# KGM_Feedback_v2_0.net
KiCad netlist of a schematic drawn in EAGLE
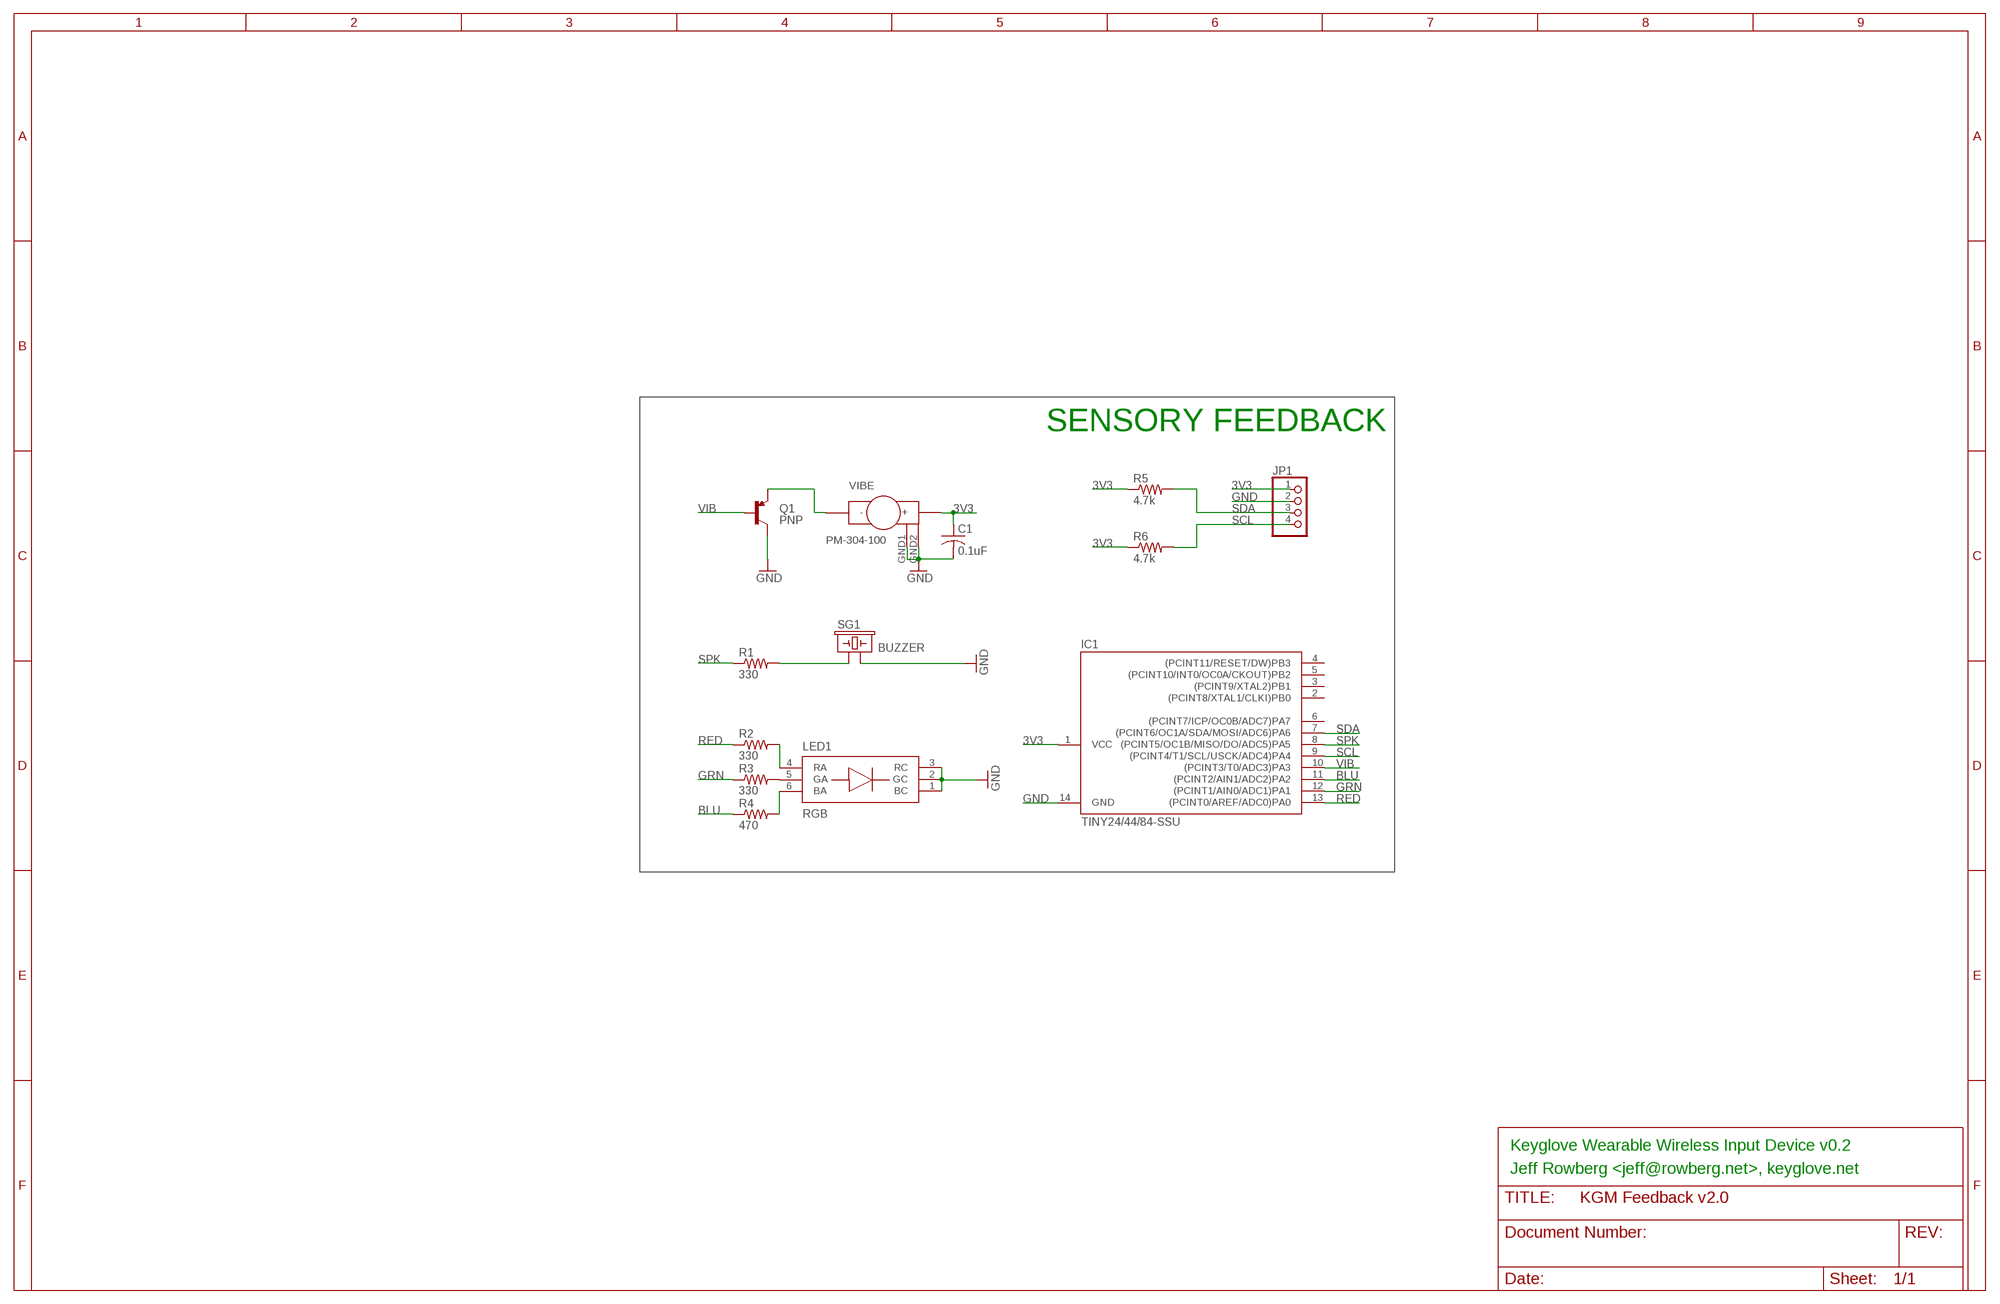
[diagram p0: schematic, sheet 1]

(export (version "E")
  (design (tool "Eeschema 10.0.6"))
  (components
    (comp (ref "C1")
      (value "0.1uF")
      (footprint "eagle-import:C0603")
      (libsource (lib "eagle-import") (part "C-USC0603"))
    )
    (comp (ref "IC1")
      (value "TINY24/44/84-SSU")
      (footprint "eagle-import:SOIC14")
      (libsource (lib "eagle-import") (part "TINY24/44/84-SSU"))
    )
    (comp (ref "JP1")
      (value "PINHD-1X4")
      (footprint "eagle-import:1X04")
      (libsource (lib "eagle-import") (part "PINHD-1X4"))
    )
    (comp (ref "LED1")
      (value "RGB")
      (footprint "eagle-import:PLCC-6")
      (libsource (lib "eagle-import") (part "ASMT-YTB2"))
    )
    (comp (ref "Q1")
      (value "PNP")
      (footprint "eagle-import:SOT23-3")
      (libsource (lib "eagle-import") (part "TRANSISTOR_PNPSMD"))
    )
    (comp (ref "R1")
      (value "330")
      (footprint "eagle-import:R0603")
      (libsource (lib "eagle-import") (part "R-US_R0603"))
    )
    (comp (ref "R2")
      (value "330")
      (footprint "eagle-import:R0603")
      (libsource (lib "eagle-import") (part "R-US_R0603"))
    )
    (comp (ref "R3")
      (value "330")
      (footprint "eagle-import:R0603")
      (libsource (lib "eagle-import") (part "R-US_R0603"))
    )
    (comp (ref "R4")
      (value "470")
      (footprint "eagle-import:R0603")
      (libsource (lib "eagle-import") (part "R-US_R0603"))
    )
    (comp (ref "R5")
      (value "4.7k")
      (footprint "eagle-import:R0603")
      (libsource (lib "eagle-import") (part "R-US_R0603"))
    )
    (comp (ref "R6")
      (value "4.7k")
      (footprint "eagle-import:R0603")
      (libsource (lib "eagle-import") (part "R-US_R0603"))
    )
    (comp (ref "SG1")
      (value "BUZZER")
      (footprint "eagle-import:BUZZER-CMT1102")
      (libsource (lib "eagle-import") (part "BUZZERSMD3"))
    )
    (comp (ref "VIBE")
      (value "PM-304-100")
      (footprint "eagle-import:PM-304-100")
      (libsource (lib "eagle-import") (part "PM-304-100"))
    )
  )
  (nets
    (net (code "1") (name "/3V3") (class "Default")
      (node (ref "C1") (pin "1") (pinfunction "1_1") (pintype "passive"))
      (node (ref "IC1") (pin "1") (pinfunction "VCC_1") (pintype "power_in"))
      (node (ref "JP1") (pin "1") (pinfunction "1_1") (pintype "passive"))
      (node (ref "R5") (pin "1") (pinfunction "1_1") (pintype "passive"))
      (node (ref "R6") (pin "1") (pinfunction "1_1") (pintype "passive"))
      (node (ref "VIBE") (pin "+") (pinfunction "+_+") (pintype "bidirectional"))
    )
    (net (code "2") (name "/BLU") (class "Default")
      (node (ref "IC1") (pin "11") (pinfunction "(PCINT2/AIN1/ADC2)PA2_11") (pintype "bidirectional"))
      (node (ref "R4") (pin "1") (pinfunction "1_1") (pintype "passive"))
    )
    (net (code "3") (name "/GRN") (class "Default")
      (node (ref "IC1") (pin "12") (pinfunction "(PCINT1/AIN0/ADC1)PA1_12") (pintype "bidirectional"))
      (node (ref "R3") (pin "1") (pinfunction "1_1") (pintype "passive"))
    )
    (net (code "4") (name "/RED") (class "Default")
      (node (ref "IC1") (pin "13") (pinfunction "(PCINT0/AREF/ADC0)PA0_13") (pintype "bidirectional"))
      (node (ref "R2") (pin "1") (pinfunction "1_1") (pintype "passive"))
    )
    (net (code "5") (name "/SCL") (class "Default")
      (node (ref "IC1") (pin "9") (pinfunction "(PCINT4/T1/SCL/USCK/ADC4)PA4_9") (pintype "bidirectional"))
      (node (ref "JP1") (pin "4") (pinfunction "4_4") (pintype "passive"))
      (node (ref "R6") (pin "2") (pinfunction "2_2") (pintype "passive"))
    )
    (net (code "6") (name "/SDA") (class "Default")
      (node (ref "IC1") (pin "7") (pinfunction "(PCINT6/OC1A/SDA/MOSI/ADC6)PA6_7") (pintype "bidirectional"))
      (node (ref "JP1") (pin "3") (pinfunction "3_3") (pintype "passive"))
      (node (ref "R5") (pin "2") (pinfunction "2_2") (pintype "passive"))
    )
    (net (code "7") (name "/SPK") (class "Default")
      (node (ref "IC1") (pin "8") (pinfunction "(PCINT5/OC1B/MISO/DO/ADC5)PA5_8") (pintype "bidirectional"))
      (node (ref "R1") (pin "1") (pinfunction "1_1") (pintype "passive"))
    )
    (net (code "8") (name "/VIB") (class "Default")
      (node (ref "IC1") (pin "10") (pinfunction "(PCINT3/T0/ADC3)PA3_10") (pintype "bidirectional"))
      (node (ref "Q1") (pin "1") (pinfunction "B_1") (pintype "passive"))
    )
    (net (code "9") (name "GND") (class "Default")
      (node (ref "C1") (pin "2") (pinfunction "2_2") (pintype "passive"))
      (node (ref "IC1") (pin "14") (pinfunction "GND_14") (pintype "power_in"))
      (node (ref "JP1") (pin "2") (pinfunction "2_2") (pintype "passive"))
      (node (ref "LED1") (pin "1") (pinfunction "BC_1") (pintype "bidirectional"))
      (node (ref "LED1") (pin "2") (pinfunction "GC_2") (pintype "bidirectional"))
      (node (ref "LED1") (pin "3") (pinfunction "RC_3") (pintype "bidirectional"))
      (node (ref "Q1") (pin "3") (pinfunction "C_3") (pintype "passive"))
      (node (ref "SG1") (pin "2") (pinfunction "2_2") (pintype "passive"))
      (node (ref "VIBE") (pin "GND1") (pinfunction "GND_GND1") (pintype "bidirectional"))
      (node (ref "VIBE") (pin "GND2") (pinfunction "GND_GND2") (pintype "bidirectional"))
    )
    (net (code "10") (name "Net-(LED1-BA)") (class "Default")
      (node (ref "LED1") (pin "6") (pinfunction "BA_6") (pintype "bidirectional"))
      (node (ref "R4") (pin "2") (pinfunction "2_2") (pintype "passive"))
    )
    (net (code "11") (name "Net-(LED1-GA)") (class "Default")
      (node (ref "LED1") (pin "5") (pinfunction "GA_5") (pintype "bidirectional"))
      (node (ref "R3") (pin "2") (pinfunction "2_2") (pintype "passive"))
    )
    (net (code "12") (name "Net-(LED1-RA)") (class "Default")
      (node (ref "LED1") (pin "4") (pinfunction "RA_4") (pintype "bidirectional"))
      (node (ref "R2") (pin "2") (pinfunction "2_2") (pintype "passive"))
    )
    (net (code "13") (name "Net-(Q1-E)") (class "Default")
      (node (ref "Q1") (pin "2") (pinfunction "E_2") (pintype "passive"))
      (node (ref "VIBE") (pin "-") (pinfunction "-_-") (pintype "bidirectional"))
    )
    (net (code "14") (name "Net-(R1-Pad2)") (class "Default")
      (node (ref "R1") (pin "2") (pinfunction "2_2") (pintype "passive"))
      (node (ref "SG1") (pin "1") (pinfunction "1_1") (pintype "passive"))
    )
    (net (code "15") (name "unconnected-(IC1-(PCINT7{slash}ICP{slash}OC0B{slash}ADC7)PA7-Pad6)") (class "Default")
      (node (ref "IC1") (pin "6") (pinfunction "(PCINT7/ICP/OC0B/ADC7)PA7_6") (pintype "bidirectional"))
    )
    (net (code "16") (name "unconnected-(IC1-(PCINT8{slash}XTAL1{slash}CLKI)PB0-Pad2)") (class "Default")
      (node (ref "IC1") (pin "2") (pinfunction "(PCINT8/XTAL1/CLKI)PB0_2") (pintype "bidirectional"))
    )
    (net (code "17") (name "unconnected-(IC1-(PCINT9{slash}XTAL2)PB1-Pad3)") (class "Default")
      (node (ref "IC1") (pin "3") (pinfunction "(PCINT9/XTAL2)PB1_3") (pintype "bidirectional"))
    )
    (net (code "18") (name "unconnected-(IC1-(PCINT10{slash}INT0{slash}OC0A{slash}CKOUT)PB2-Pad5)") (class "Default")
      (node (ref "IC1") (pin "5") (pinfunction "(PCINT10/INT0/OC0A/CKOUT)PB2_5") (pintype "bidirectional"))
    )
    (net (code "19") (name "unconnected-(IC1-(PCINT11{slash}RESET{slash}DW)PB3-Pad4)") (class "Default")
      (node (ref "IC1") (pin "4") (pinfunction "(PCINT11/RESET/DW)PB3_4") (pintype "bidirectional"))
    )
  )
)
